# Aux_Board_V5.net
KiCad netlist of a schematic drawn in EAGLE
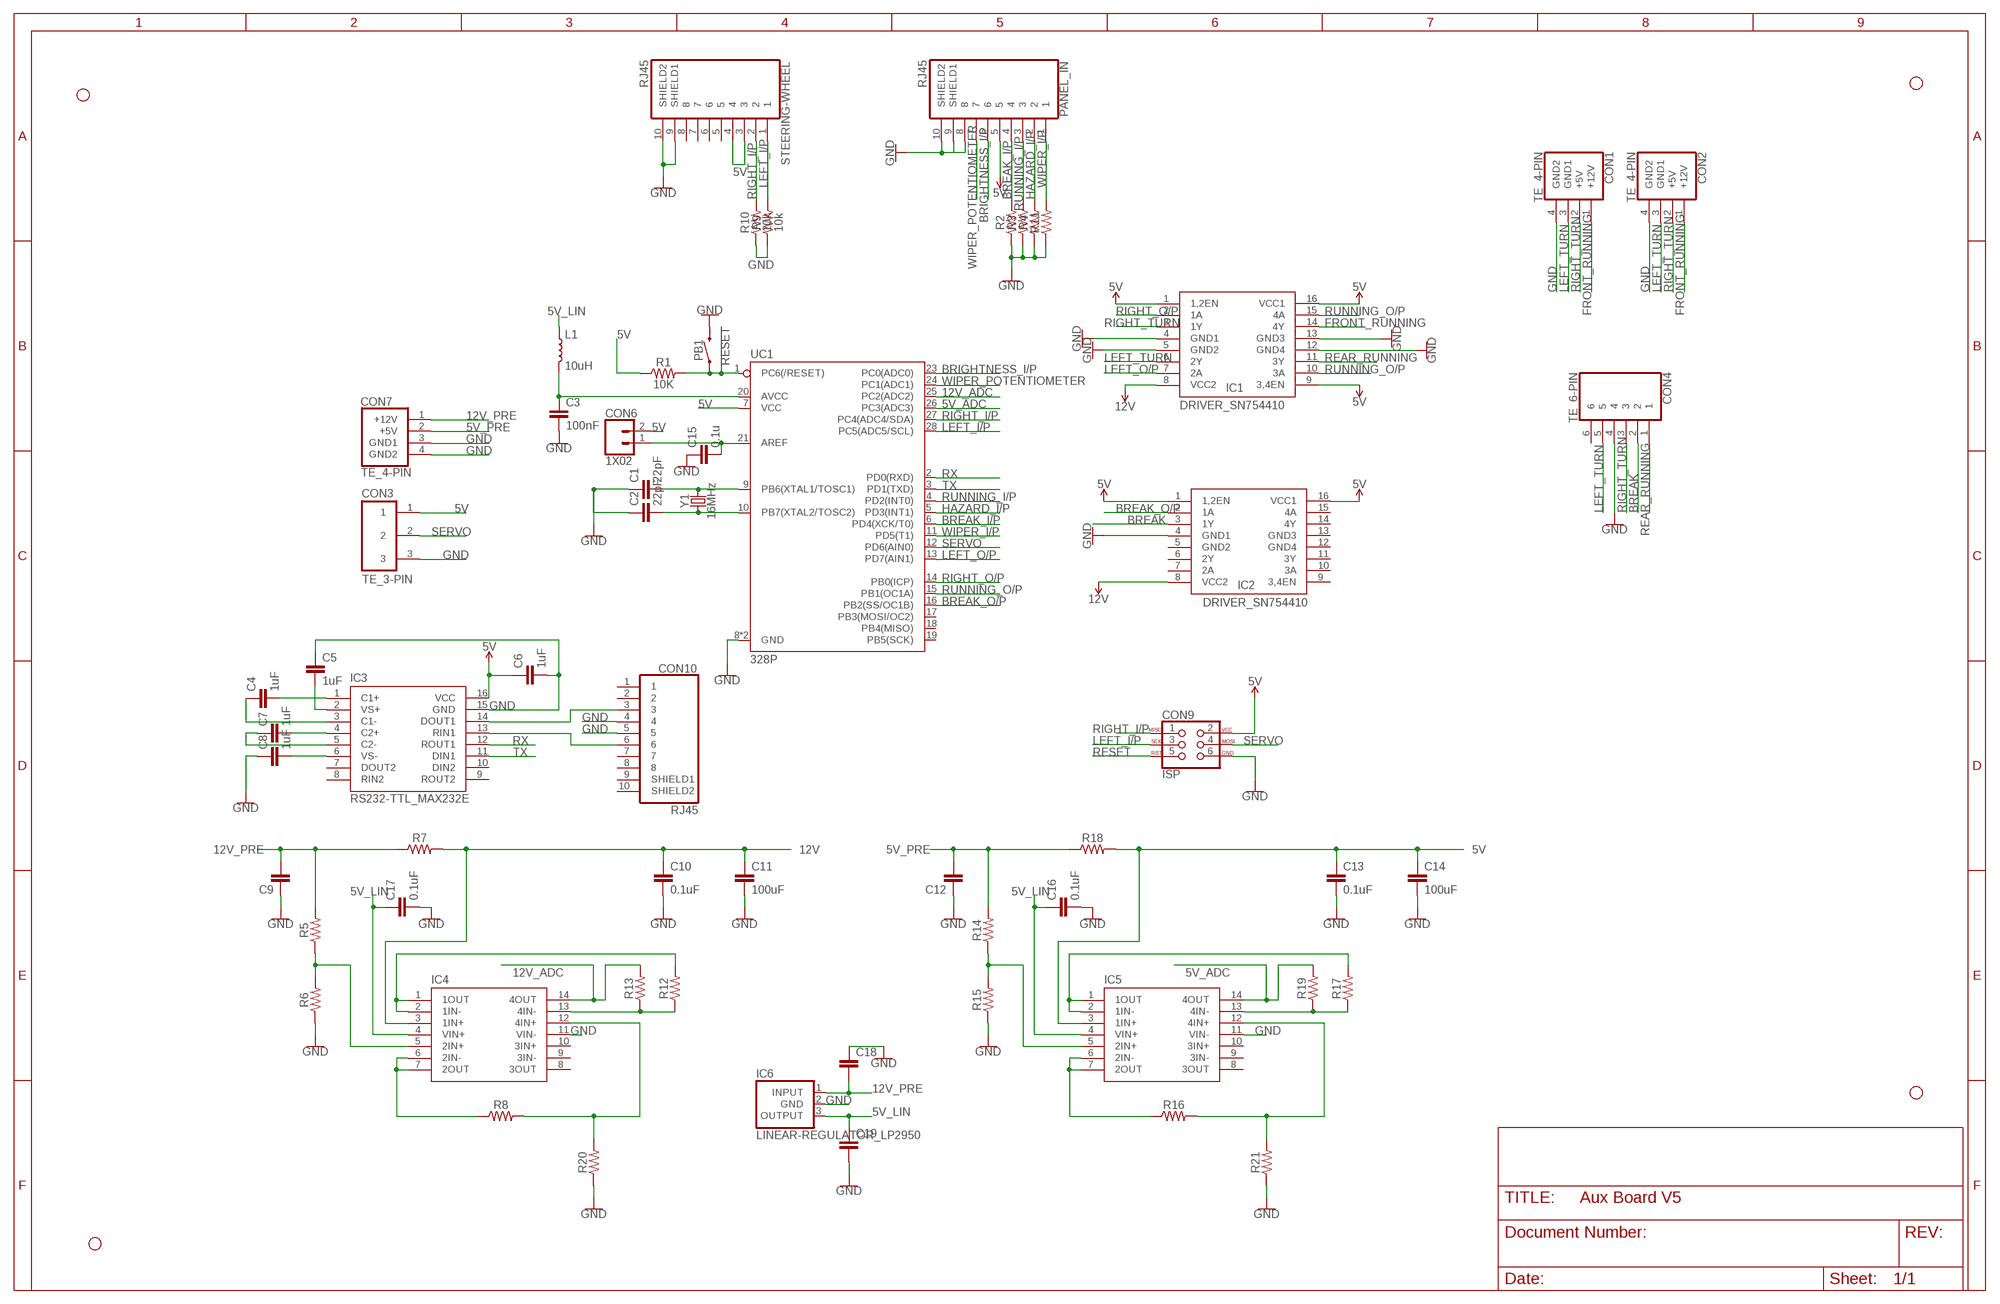
[diagram p0: schematic, sheet 1]

(export (version "E")
  (design (tool "Eeschema 10.0.6"))
  (components
    (comp (ref "C1")
      (value "22pF")
      (footprint "eagle-import:0805")
      (libsource (lib "eagle-import") (part "CAPACITOR_0805"))
    )
    (comp (ref "C2")
      (value "22pF")
      (footprint "eagle-import:0805")
      (libsource (lib "eagle-import") (part "CAPACITOR_0805"))
    )
    (comp (ref "C3")
      (value "100nF")
      (footprint "eagle-import:0805")
      (libsource (lib "eagle-import") (part "CAPACITOR_0805"))
    )
    (comp (ref "C4")
      (value "1uF")
      (footprint "eagle-import:0805")
      (libsource (lib "eagle-import") (part "CAPACITOR_0805"))
    )
    (comp (ref "C5")
      (value "1uF")
      (footprint "eagle-import:0805")
      (libsource (lib "eagle-import") (part "CAPACITOR_0805"))
    )
    (comp (ref "C6")
      (value "1uF")
      (footprint "eagle-import:0805")
      (libsource (lib "eagle-import") (part "CAPACITOR_0805"))
    )
    (comp (ref "C7")
      (value "1uF")
      (footprint "eagle-import:0805")
      (libsource (lib "eagle-import") (part "CAPACITOR_0805"))
    )
    (comp (ref "C8")
      (value "1uF")
      (footprint "eagle-import:0805")
      (libsource (lib "eagle-import") (part "CAPACITOR_0805"))
    )
    (comp (ref "C9")
      (value "CAPACITOR_0805")
      (footprint "eagle-import:0805")
      (libsource (lib "eagle-import") (part "CAPACITOR_0805"))
    )
    (comp (ref "C10")
      (value "0.1uF")
      (footprint "eagle-import:0805")
      (libsource (lib "eagle-import") (part "CAPACITOR_0805"))
    )
    (comp (ref "C11")
      (value "100uF")
      (footprint "eagle-import:0805")
      (libsource (lib "eagle-import") (part "CAPACITOR_0805"))
    )
    (comp (ref "C12")
      (value "CAPACITOR_0805")
      (footprint "eagle-import:0805")
      (libsource (lib "eagle-import") (part "CAPACITOR_0805"))
    )
    (comp (ref "C13")
      (value "0.1uF")
      (footprint "eagle-import:0805")
      (libsource (lib "eagle-import") (part "CAPACITOR_0805"))
    )
    (comp (ref "C14")
      (value "100uF")
      (footprint "eagle-import:0805")
      (libsource (lib "eagle-import") (part "CAPACITOR_0805"))
    )
    (comp (ref "C15")
      (value "0.1u")
      (footprint "eagle-import:0805")
      (libsource (lib "eagle-import") (part "CAPACITOR_0805"))
    )
    (comp (ref "C16")
      (value "0.1uF")
      (footprint "eagle-import:0805")
      (libsource (lib "eagle-import") (part "CAPACITOR_0805"))
    )
    (comp (ref "C17")
      (value "0.1uF")
      (footprint "eagle-import:0805")
      (libsource (lib "eagle-import") (part "CAPACITOR_0805"))
    )
    (comp (ref "C18")
      (value "CAPACITOR_0805")
      (footprint "eagle-import:0805")
      (libsource (lib "eagle-import") (part "CAPACITOR_0805"))
    )
    (comp (ref "C19")
      (value "CAPACITOR_0805")
      (footprint "eagle-import:0805")
      (libsource (lib "eagle-import") (part "CAPACITOR_0805"))
    )
    (comp (ref "CON1")
      (value "TE_4-PIN")
      (footprint "eagle-import:TE_4-PIN")
      (libsource (lib "eagle-import") (part "TE_4-PIN"))
    )
    (comp (ref "CON2")
      (value "TE_4-PIN")
      (footprint "eagle-import:TE_4-PIN")
      (libsource (lib "eagle-import") (part "TE_4-PIN"))
    )
    (comp (ref "CON3")
      (value "TE_3-PIN")
      (footprint "eagle-import:TE_3-PIN")
      (libsource (lib "eagle-import") (part "TE_3-PIN"))
    )
    (comp (ref "CON4")
      (value "TE_6-PIN")
      (footprint "eagle-import:TE_6-PIN")
      (libsource (lib "eagle-import") (part "TE_6-PIN"))
    )
    (comp (ref "CON6")
      (value "1X02")
      (footprint "eagle-import:1X02")
      (libsource (lib "eagle-import") (part "1X02"))
    )
    (comp (ref "CON7")
      (value "TE_4-PIN")
      (footprint "eagle-import:TE_4-PIN")
      (libsource (lib "eagle-import") (part "TE_4-PIN"))
    )
    (comp (ref "CON9")
      (value "ISP")
      (footprint "eagle-import:ISP_CONNECTOR")
      (libsource (lib "eagle-import") (part "ISP"))
    )
    (comp (ref "CON10")
      (value "RJ45")
      (footprint "eagle-import:RJ45")
      (libsource (lib "eagle-import") (part "RJ45"))
    )
    (comp (ref "H1")
      (value "STAND-OFF")
      (footprint "eagle-import:STAND-OFF")
      (libsource (lib "eagle-import") (part "STAND-OFF"))
    )
    (comp (ref "H2")
      (value "STAND-OFF")
      (footprint "eagle-import:STAND-OFF")
      (libsource (lib "eagle-import") (part "STAND-OFF"))
    )
    (comp (ref "H3")
      (value "STAND-OFF")
      (footprint "eagle-import:STAND-OFF")
      (libsource (lib "eagle-import") (part "STAND-OFF"))
    )
    (comp (ref "H4")
      (value "STAND-OFF")
      (footprint "eagle-import:STAND-OFF")
      (libsource (lib "eagle-import") (part "STAND-OFF"))
    )
    (comp (ref "IC1")
      (value "DRIVER_SN754410")
      (footprint "eagle-import:DIP16")
      (libsource (lib "eagle-import") (part "DRIVER_SN754410"))
    )
    (comp (ref "IC2")
      (value "DRIVER_SN754410")
      (footprint "eagle-import:DIP16")
      (libsource (lib "eagle-import") (part "DRIVER_SN754410"))
    )
    (comp (ref "IC3")
      (value "RS232-TTL_MAX232E")
      (footprint "eagle-import:DIP16")
      (libsource (lib "eagle-import") (part "RS232-TTL_MAX232E"))
    )
    (comp (ref "IC4")
      (value "OP-AMP_QUAD")
      (footprint "eagle-import:DIP14")
      (libsource (lib "eagle-import") (part "OP-AMP_QUAD"))
    )
    (comp (ref "IC5")
      (value "OP-AMP_QUAD")
      (footprint "eagle-import:DIP14")
      (libsource (lib "eagle-import") (part "OP-AMP_QUAD"))
    )
    (comp (ref "IC6")
      (value "LINEAR-REGULATOR_LP2950")
      (footprint "eagle-import:TO92")
      (libsource (lib "eagle-import") (part "LINEAR-REGULATOR_LP2950"))
    )
    (comp (ref "L1")
      (value "10uH")
      (footprint "eagle-import:0805")
      (libsource (lib "eagle-import") (part "INDUCTOR_0805"))
    )
    (comp (ref "PANEL_IN")
      (value "RJ45")
      (footprint "eagle-import:RJ45")
      (libsource (lib "eagle-import") (part "RJ45"))
    )
    (comp (ref "PB1")
      (value "PUSHBUTTON")
      (footprint "eagle-import:PUSHBUTTON")
      (libsource (lib "eagle-import") (part "PUSHBUTTON"))
    )
    (comp (ref "R1")
      (value "10K")
      (footprint "eagle-import:0805")
      (libsource (lib "eagle-import") (part "RESISTOR_0805"))
    )
    (comp (ref "R2")
      (value "RESISTOR_0805")
      (footprint "eagle-import:0805")
      (libsource (lib "eagle-import") (part "RESISTOR_0805"))
    )
    (comp (ref "R3")
      (value "RESISTOR_0805")
      (footprint "eagle-import:0805")
      (libsource (lib "eagle-import") (part "RESISTOR_0805"))
    )
    (comp (ref "R4")
      (value "RESISTOR_0805")
      (footprint "eagle-import:0805")
      (libsource (lib "eagle-import") (part "RESISTOR_0805"))
    )
    (comp (ref "R5")
      (value "RESISTOR_0805")
      (footprint "eagle-import:0805")
      (libsource (lib "eagle-import") (part "RESISTOR_0805"))
    )
    (comp (ref "R6")
      (value "RESISTOR_0805")
      (footprint "eagle-import:0805")
      (libsource (lib "eagle-import") (part "RESISTOR_0805"))
    )
    (comp (ref "R7")
      (value "RESISTOR_1210")
      (footprint "eagle-import:1210")
      (libsource (lib "eagle-import") (part "RESISTOR_1210"))
    )
    (comp (ref "R8")
      (value "RESISTOR_0805")
      (footprint "eagle-import:0805")
      (libsource (lib "eagle-import") (part "RESISTOR_0805"))
    )
    (comp (ref "R9")
      (value "10k")
      (footprint "eagle-import:0805")
      (libsource (lib "eagle-import") (part "RESISTOR_0805"))
    )
    (comp (ref "R10")
      (value "10k")
      (footprint "eagle-import:0805")
      (libsource (lib "eagle-import") (part "RESISTOR_0805"))
    )
    (comp (ref "R11")
      (value "RESISTOR_0805")
      (footprint "eagle-import:0805")
      (libsource (lib "eagle-import") (part "RESISTOR_0805"))
    )
    (comp (ref "R12")
      (value "RESISTOR_0805")
      (footprint "eagle-import:0805")
      (libsource (lib "eagle-import") (part "RESISTOR_0805"))
    )
    (comp (ref "R13")
      (value "RESISTOR_0805")
      (footprint "eagle-import:0805")
      (libsource (lib "eagle-import") (part "RESISTOR_0805"))
    )
    (comp (ref "R14")
      (value "RESISTOR_0805")
      (footprint "eagle-import:0805")
      (libsource (lib "eagle-import") (part "RESISTOR_0805"))
    )
    (comp (ref "R15")
      (value "RESISTOR_0805")
      (footprint "eagle-import:0805")
      (libsource (lib "eagle-import") (part "RESISTOR_0805"))
    )
    (comp (ref "R16")
      (value "RESISTOR_0805")
      (footprint "eagle-import:0805")
      (libsource (lib "eagle-import") (part "RESISTOR_0805"))
    )
    (comp (ref "R17")
      (value "RESISTOR_0805")
      (footprint "eagle-import:0805")
      (libsource (lib "eagle-import") (part "RESISTOR_0805"))
    )
    (comp (ref "R18")
      (value "RESISTOR_1210")
      (footprint "eagle-import:1210")
      (libsource (lib "eagle-import") (part "RESISTOR_1210"))
    )
    (comp (ref "R19")
      (value "RESISTOR_0805")
      (footprint "eagle-import:0805")
      (libsource (lib "eagle-import") (part "RESISTOR_0805"))
    )
    (comp (ref "R20")
      (value "RESISTOR_0805")
      (footprint "eagle-import:0805")
      (libsource (lib "eagle-import") (part "RESISTOR_0805"))
    )
    (comp (ref "R21")
      (value "RESISTOR_0805")
      (footprint "eagle-import:0805")
      (libsource (lib "eagle-import") (part "RESISTOR_0805"))
    )
    (comp (ref "STEERING-WHEEL")
      (value "RJ45")
      (footprint "eagle-import:RJ45")
      (libsource (lib "eagle-import") (part "RJ45"))
    )
    (comp (ref "UC1")
      (value "328P")
      (footprint "eagle-import:DIP28")
      (libsource (lib "eagle-import") (part "ATMEGA328P_DIP28"))
    )
    (comp (ref "Y1")
      (value "16MHz")
      (footprint "eagle-import:HC49US")
      (libsource (lib "eagle-import") (part "CRYSTAL-16MHZPTH-HC49US"))
    )
  )
  (nets
    (net (code "1") (name "/5V_ADC") (class "Default")
      (node (ref "IC5") (pin "14") (pinfunction "4OUT_14") (pintype "bidirectional"))
      (node (ref "R19") (pin "2") (pinfunction "2_2") (pintype "passive"))
      (node (ref "UC1") (pin "26") (pinfunction "PC3(ADC3)_26") (pintype "bidirectional"))
    )
    (net (code "2") (name "/5V_LIN") (class "Default")
      (node (ref "C16") (pin "1") (pinfunction "1_1") (pintype "passive"))
      (node (ref "C17") (pin "1") (pinfunction "1_1") (pintype "passive"))
      (node (ref "C19") (pin "1") (pinfunction "1_1") (pintype "passive"))
      (node (ref "IC4") (pin "4") (pinfunction "VIN+_4") (pintype "bidirectional"))
      (node (ref "IC5") (pin "4") (pinfunction "VIN+_4") (pintype "bidirectional"))
      (node (ref "IC6") (pin "3") (pinfunction "OUTPUT_3") (pintype "bidirectional"))
      (node (ref "L1") (pin "1") (pinfunction "1_1") (pintype "passive"))
    )
    (net (code "3") (name "/5V_PRE") (class "Default")
      (node (ref "C12") (pin "2") (pinfunction "2_2") (pintype "passive"))
      (node (ref "CON7") (pin "2") (pinfunction "+5V_2") (pintype "passive"))
      (node (ref "R14") (pin "2") (pinfunction "2_2") (pintype "passive"))
      (node (ref "R18") (pin "1") (pinfunction "1_1") (pintype "passive"))
    )
    (net (code "4") (name "/12V_ADC") (class "Default")
      (node (ref "IC4") (pin "14") (pinfunction "4OUT_14") (pintype "bidirectional"))
      (node (ref "R13") (pin "2") (pinfunction "2_2") (pintype "passive"))
      (node (ref "UC1") (pin "25") (pinfunction "PC2(ADC2)_25") (pintype "bidirectional"))
    )
    (net (code "5") (name "/12V_PRE") (class "Default")
      (node (ref "C18") (pin "2") (pinfunction "2_2") (pintype "passive"))
      (node (ref "C9") (pin "2") (pinfunction "2_2") (pintype "passive"))
      (node (ref "CON7") (pin "1") (pinfunction "+12V_1") (pintype "passive"))
      (node (ref "IC6") (pin "1") (pinfunction "INPUT_1") (pintype "bidirectional"))
      (node (ref "R5") (pin "2") (pinfunction "2_2") (pintype "passive"))
      (node (ref "R7") (pin "1") (pinfunction "1_1") (pintype "passive"))
    )
    (net (code "6") (name "/BREAK") (class "Default")
      (node (ref "CON4") (pin "2") (pinfunction "2_2") (pintype "passive"))
      (node (ref "IC2") (pin "3") (pinfunction "1Y_3") (pintype "bidirectional"))
    )
    (net (code "7") (name "/BREAK_I{slash}P") (class "Default")
      (node (ref "PANEL_IN") (pin "4") (pinfunction "4_4") (pintype "passive"))
      (node (ref "R2") (pin "2") (pinfunction "2_2") (pintype "passive"))
      (node (ref "UC1") (pin "6") (pinfunction "PD4(XCK/T0)_6") (pintype "bidirectional"))
    )
    (net (code "8") (name "/BREAK_O{slash}P") (class "Default")
      (node (ref "IC2") (pin "2") (pinfunction "1A_2") (pintype "bidirectional"))
      (node (ref "UC1") (pin "16") (pinfunction "PB2(SS/OC1B)_16") (pintype "bidirectional"))
    )
    (net (code "9") (name "/BRIGHTNESS_I{slash}P") (class "Default")
      (node (ref "PANEL_IN") (pin "6") (pinfunction "6_6") (pintype "passive"))
      (node (ref "UC1") (pin "23") (pinfunction "PC0(ADC0)_23") (pintype "bidirectional"))
    )
    (net (code "10") (name "/FRONT_RUNNING") (class "Default")
      (node (ref "CON1") (pin "1") (pinfunction "+12V_1") (pintype "passive"))
      (node (ref "CON2") (pin "1") (pinfunction "+12V_1") (pintype "passive"))
      (node (ref "IC1") (pin "14") (pinfunction "4Y_14") (pintype "bidirectional"))
    )
    (net (code "11") (name "/HAZARD_I{slash}P") (class "Default")
      (node (ref "PANEL_IN") (pin "2") (pinfunction "2_2") (pintype "passive"))
      (node (ref "R4") (pin "2") (pinfunction "2_2") (pintype "passive"))
      (node (ref "UC1") (pin "5") (pinfunction "PD3(INT1)_5") (pintype "bidirectional"))
    )
    (net (code "12") (name "/LEFT_I{slash}P") (class "Default")
      (node (ref "CON9") (pin "3") (pinfunction "3_3") (pintype "passive"))
      (node (ref "R9") (pin "2") (pinfunction "2_2") (pintype "passive"))
      (node (ref "STEERING-WHEEL") (pin "1") (pinfunction "1_1") (pintype "passive"))
      (node (ref "UC1") (pin "28") (pinfunction "PC5(ADC5/SCL)_28") (pintype "bidirectional"))
    )
    (net (code "13") (name "/LEFT_O{slash}P") (class "Default")
      (node (ref "IC1") (pin "7") (pinfunction "2A_7") (pintype "bidirectional"))
      (node (ref "UC1") (pin "13") (pinfunction "PD7(AIN1)_13") (pintype "bidirectional"))
    )
    (net (code "14") (name "/LEFT_TURN") (class "Default")
      (node (ref "CON1") (pin "3") (pinfunction "GND1_3") (pintype "passive"))
      (node (ref "CON2") (pin "3") (pinfunction "GND1_3") (pintype "passive"))
      (node (ref "CON4") (pin "5") (pinfunction "5_5") (pintype "passive"))
      (node (ref "IC1") (pin "6") (pinfunction "2Y_6") (pintype "bidirectional"))
    )
    (net (code "15") (name "/REAR_RUNNING") (class "Default")
      (node (ref "CON4") (pin "1") (pinfunction "1_1") (pintype "passive"))
      (node (ref "IC1") (pin "11") (pinfunction "3Y_11") (pintype "bidirectional"))
    )
    (net (code "16") (name "/RESET") (class "Default")
      (node (ref "CON9") (pin "5") (pinfunction "5_5") (pintype "passive"))
      (node (ref "PB1") (pin "1") (pinfunction "1_1") (pintype "passive"))
      (node (ref "PB1") (pin "2") (pinfunction "1_2") (pintype "passive"))
      (node (ref "R1") (pin "2") (pinfunction "2_2") (pintype "passive"))
      (node (ref "UC1") (pin "1") (pinfunction "PC6(/RESET)_1") (pintype "bidirectional"))
    )
    (net (code "17") (name "/RIGHT_I{slash}P") (class "Default")
      (node (ref "CON9") (pin "1") (pinfunction "1_1") (pintype "passive"))
      (node (ref "R10") (pin "2") (pinfunction "2_2") (pintype "passive"))
      (node (ref "STEERING-WHEEL") (pin "2") (pinfunction "2_2") (pintype "passive"))
      (node (ref "UC1") (pin "27") (pinfunction "PC4(ADC4/SDA)_27") (pintype "bidirectional"))
    )
    (net (code "18") (name "/RIGHT_O{slash}P") (class "Default")
      (node (ref "IC1") (pin "2") (pinfunction "1A_2") (pintype "bidirectional"))
      (node (ref "UC1") (pin "14") (pinfunction "PB0(ICP)_14") (pintype "bidirectional"))
    )
    (net (code "19") (name "/RIGHT_TURN") (class "Default")
      (node (ref "CON1") (pin "2") (pinfunction "+5V_2") (pintype "passive"))
      (node (ref "CON2") (pin "2") (pinfunction "+5V_2") (pintype "passive"))
      (node (ref "CON4") (pin "3") (pinfunction "3_3") (pintype "passive"))
      (node (ref "IC1") (pin "3") (pinfunction "1Y_3") (pintype "bidirectional"))
    )
    (net (code "20") (name "/RUNNING_I{slash}P") (class "Default")
      (node (ref "PANEL_IN") (pin "3") (pinfunction "3_3") (pintype "passive"))
      (node (ref "R3") (pin "2") (pinfunction "2_2") (pintype "passive"))
      (node (ref "UC1") (pin "4") (pinfunction "PD2(INT0)_4") (pintype "bidirectional"))
    )
    (net (code "21") (name "/RUNNING_O{slash}P") (class "Default")
      (node (ref "IC1") (pin "10") (pinfunction "3A_10") (pintype "bidirectional"))
      (node (ref "IC1") (pin "15") (pinfunction "4A_15") (pintype "bidirectional"))
      (node (ref "UC1") (pin "15") (pinfunction "PB1(OC1A)_15") (pintype "bidirectional"))
    )
    (net (code "22") (name "/RX") (class "Default")
      (node (ref "IC3") (pin "12") (pinfunction "ROUT1_12") (pintype "bidirectional"))
      (node (ref "UC1") (pin "2") (pinfunction "PD0(RXD)_2") (pintype "bidirectional"))
    )
    (net (code "23") (name "/SERVO") (class "Default")
      (node (ref "CON3") (pin "2") (pinfunction "2_2") (pintype "passive"))
      (node (ref "CON9") (pin "4") (pinfunction "4_4") (pintype "passive"))
      (node (ref "UC1") (pin "12") (pinfunction "PD6(AIN0)_12") (pintype "bidirectional"))
    )
    (net (code "24") (name "/TX") (class "Default")
      (node (ref "IC3") (pin "11") (pinfunction "DIN1_11") (pintype "bidirectional"))
      (node (ref "UC1") (pin "3") (pinfunction "PD1(TXD)_3") (pintype "bidirectional"))
    )
    (net (code "25") (name "/WIPER_I{slash}P") (class "Default")
      (node (ref "PANEL_IN") (pin "1") (pinfunction "1_1") (pintype "passive"))
      (node (ref "R11") (pin "2") (pinfunction "2_2") (pintype "passive"))
      (node (ref "UC1") (pin "11") (pinfunction "PD5(T1)_11") (pintype "bidirectional"))
    )
    (net (code "26") (name "/WIPER_POTENTIOMETER") (class "Default")
      (node (ref "PANEL_IN") (pin "7") (pinfunction "7_7") (pintype "passive"))
      (node (ref "UC1") (pin "24") (pinfunction "PC1(ADC1)_24") (pintype "bidirectional"))
    )
    (net (code "27") (name "5V") (class "Default")
      (node (ref "C13") (pin "1") (pinfunction "1_1") (pintype "passive"))
      (node (ref "C14") (pin "1") (pinfunction "1_1") (pintype "passive"))
      (node (ref "C15") (pin "2") (pinfunction "2_2") (pintype "passive"))
      (node (ref "C6") (pin "1") (pinfunction "1_1") (pintype "passive"))
      (node (ref "CON3") (pin "1") (pinfunction "1_1") (pintype "passive"))
      (node (ref "CON6") (pin "1") (pinfunction "1_1") (pintype "passive"))
      (node (ref "CON6") (pin "2") (pinfunction "2_2") (pintype "passive"))
      (node (ref "CON9") (pin "2") (pinfunction "2_2") (pintype "passive"))
      (node (ref "IC1") (pin "1") (pinfunction "1,2EN_1") (pintype "bidirectional"))
      (node (ref "IC1") (pin "16") (pinfunction "VCC1_16") (pintype "bidirectional"))
      (node (ref "IC1") (pin "9") (pinfunction "3,4EN_9") (pintype "bidirectional"))
      (node (ref "IC2") (pin "1") (pinfunction "1,2EN_1") (pintype "bidirectional"))
      (node (ref "IC2") (pin "16") (pinfunction "VCC1_16") (pintype "bidirectional"))
      (node (ref "IC3") (pin "16") (pinfunction "VCC_16") (pintype "bidirectional"))
      (node (ref "IC5") (pin "3") (pinfunction "1IN+_3") (pintype "bidirectional"))
      (node (ref "PANEL_IN") (pin "5") (pinfunction "5_5") (pintype "passive"))
      (node (ref "R1") (pin "1") (pinfunction "1_1") (pintype "passive"))
      (node (ref "R18") (pin "2") (pinfunction "2_2") (pintype "passive"))
      (node (ref "STEERING-WHEEL") (pin "3") (pinfunction "3_3") (pintype "passive"))
      (node (ref "STEERING-WHEEL") (pin "4") (pinfunction "4_4") (pintype "passive"))
      (node (ref "UC1") (pin "21") (pinfunction "AREF_21") (pintype "bidirectional"))
      (node (ref "UC1") (pin "7") (pinfunction "VCC_7") (pintype "bidirectional"))
    )
    (net (code "28") (name "12V") (class "Default")
      (node (ref "C10") (pin "1") (pinfunction "1_1") (pintype "passive"))
      (node (ref "C11") (pin "1") (pinfunction "1_1") (pintype "passive"))
      (node (ref "IC1") (pin "8") (pinfunction "VCC2_8") (pintype "bidirectional"))
      (node (ref "IC2") (pin "8") (pinfunction "VCC2_8") (pintype "bidirectional"))
      (node (ref "IC4") (pin "3") (pinfunction "1IN+_3") (pintype "bidirectional"))
      (node (ref "R7") (pin "2") (pinfunction "2_2") (pintype "passive"))
    )
    (net (code "29") (name "GND") (class "Default")
      (node (ref "C1") (pin "1") (pinfunction "1_1") (pintype "passive"))
      (node (ref "C10") (pin "2") (pinfunction "2_2") (pintype "passive"))
      (node (ref "C11") (pin "2") (pinfunction "2_2") (pintype "passive"))
      (node (ref "C12") (pin "1") (pinfunction "1_1") (pintype "passive"))
      (node (ref "C13") (pin "2") (pinfunction "2_2") (pintype "passive"))
      (node (ref "C14") (pin "2") (pinfunction "2_2") (pintype "passive"))
      (node (ref "C15") (pin "1") (pinfunction "1_1") (pintype "passive"))
      (node (ref "C16") (pin "2") (pinfunction "2_2") (pintype "passive"))
      (node (ref "C17") (pin "2") (pinfunction "2_2") (pintype "passive"))
      (node (ref "C18") (pin "1") (pinfunction "1_1") (pintype "passive"))
      (node (ref "C19") (pin "2") (pinfunction "2_2") (pintype "passive"))
      (node (ref "C2") (pin "1") (pinfunction "1_1") (pintype "passive"))
      (node (ref "C3") (pin "2") (pinfunction "2_2") (pintype "passive"))
      (node (ref "C5") (pin "1") (pinfunction "1_1") (pintype "passive"))
      (node (ref "C6") (pin "2") (pinfunction "2_2") (pintype "passive"))
      (node (ref "C8") (pin "1") (pinfunction "1_1") (pintype "passive"))
      (node (ref "C9") (pin "1") (pinfunction "1_1") (pintype "passive"))
      (node (ref "CON1") (pin "4") (pinfunction "GND2_4") (pintype "passive"))
      (node (ref "CON10") (pin "4") (pinfunction "4_4") (pintype "passive"))
      (node (ref "CON10") (pin "5") (pinfunction "5_5") (pintype "passive"))
      (node (ref "CON2") (pin "4") (pinfunction "GND2_4") (pintype "passive"))
      (node (ref "CON3") (pin "3") (pinfunction "3_3") (pintype "passive"))
      (node (ref "CON4") (pin "4") (pinfunction "4_4") (pintype "passive"))
      (node (ref "CON7") (pin "3") (pinfunction "GND1_3") (pintype "passive"))
      (node (ref "CON7") (pin "4") (pinfunction "GND2_4") (pintype "passive"))
      (node (ref "CON9") (pin "6") (pinfunction "6_6") (pintype "passive"))
      (node (ref "IC1") (pin "12") (pinfunction "GND4_12") (pintype "bidirectional"))
      (node (ref "IC1") (pin "13") (pinfunction "GND3_13") (pintype "bidirectional"))
      (node (ref "IC1") (pin "4") (pinfunction "GND1_4") (pintype "bidirectional"))
      (node (ref "IC1") (pin "5") (pinfunction "GND2_5") (pintype "bidirectional"))
      (node (ref "IC2") (pin "4") (pinfunction "GND1_4") (pintype "bidirectional"))
      (node (ref "IC3") (pin "15") (pinfunction "GND_15") (pintype "bidirectional"))
      (node (ref "IC4") (pin "11") (pinfunction "VIN-_11") (pintype "bidirectional"))
      (node (ref "IC5") (pin "11") (pinfunction "VIN-_11") (pintype "bidirectional"))
      (node (ref "IC6") (pin "2") (pinfunction "GND_2") (pintype "bidirectional"))
      (node (ref "PANEL_IN") (pin "10") (pinfunction "SHIELD2_10") (pintype "passive"))
      (node (ref "PANEL_IN") (pin "8") (pinfunction "8_8") (pintype "passive"))
      (node (ref "PANEL_IN") (pin "9") (pinfunction "SHIELD1_9") (pintype "passive"))
      (node (ref "PB1") (pin "3") (pinfunction "2_3") (pintype "passive"))
      (node (ref "PB1") (pin "4") (pinfunction "2_4") (pintype "passive"))
      (node (ref "R10") (pin "1") (pinfunction "1_1") (pintype "passive"))
      (node (ref "R11") (pin "1") (pinfunction "1_1") (pintype "passive"))
      (node (ref "R15") (pin "1") (pinfunction "1_1") (pintype "passive"))
      (node (ref "R2") (pin "1") (pinfunction "1_1") (pintype "passive"))
      (node (ref "R20") (pin "1") (pinfunction "1_1") (pintype "passive"))
      (node (ref "R21") (pin "1") (pinfunction "1_1") (pintype "passive"))
      (node (ref "R3") (pin "1") (pinfunction "1_1") (pintype "passive"))
      (node (ref "R4") (pin "1") (pinfunction "1_1") (pintype "passive"))
      (node (ref "R6") (pin "1") (pinfunction "1_1") (pintype "passive"))
      (node (ref "R9") (pin "1") (pinfunction "1_1") (pintype "passive"))
      (node (ref "STEERING-WHEEL") (pin "10") (pinfunction "SHIELD2_10") (pintype "passive"))
      (node (ref "STEERING-WHEEL") (pin "9") (pinfunction "SHIELD1_9") (pintype "passive"))
      (node (ref "UC1") (pin "22") (pinfunction "GND_22") (pintype "bidirectional"))
      (node (ref "UC1") (pin "8") (pinfunction "GND_8") (pintype "bidirectional"))
    )
    (net (code "30") (name "Net-(IC3-C1+)") (class "Default")
      (node (ref "C4") (pin "2") (pinfunction "2_2") (pintype "passive"))
      (node (ref "IC3") (pin "1") (pinfunction "C1+_1") (pintype "bidirectional"))
    )
    (net (code "31") (name "Net-(IC3-C1-)") (class "Default")
      (node (ref "C4") (pin "1") (pinfunction "1_1") (pintype "passive"))
      (node (ref "IC3") (pin "3") (pinfunction "C1-_3") (pintype "bidirectional"))
    )
    (net (code "32") (name "Net-(IC3-C2+)") (class "Default")
      (node (ref "C7") (pin "2") (pinfunction "2_2") (pintype "passive"))
      (node (ref "IC3") (pin "4") (pinfunction "C2+_4") (pintype "bidirectional"))
    )
    (net (code "33") (name "Net-(IC3-C2-)") (class "Default")
      (node (ref "C7") (pin "1") (pinfunction "1_1") (pintype "passive"))
      (node (ref "IC3") (pin "5") (pinfunction "C2-_5") (pintype "bidirectional"))
    )
    (net (code "34") (name "Net-(IC3-DOUT1)") (class "Default")
      (node (ref "CON10") (pin "3") (pinfunction "3_3") (pintype "passive"))
      (node (ref "IC3") (pin "14") (pinfunction "DOUT1_14") (pintype "bidirectional"))
    )
    (net (code "35") (name "Net-(IC3-RIN1)") (class "Default")
      (node (ref "CON10") (pin "6") (pinfunction "6_6") (pintype "passive"))
      (node (ref "IC3") (pin "13") (pinfunction "RIN1_13") (pintype "bidirectional"))
    )
    (net (code "36") (name "Net-(IC3-VS+)") (class "Default")
      (node (ref "C5") (pin "2") (pinfunction "2_2") (pintype "passive"))
      (node (ref "IC3") (pin "2") (pinfunction "VS+_2") (pintype "bidirectional"))
    )
    (net (code "37") (name "Net-(IC3-VS-)") (class "Default")
      (node (ref "C8") (pin "2") (pinfunction "2_2") (pintype "passive"))
      (node (ref "IC3") (pin "6") (pinfunction "VS-_6") (pintype "bidirectional"))
    )
    (net (code "38") (name "Net-(IC4-1IN-)") (class "Default")
      (node (ref "IC4") (pin "1") (pinfunction "1OUT_1") (pintype "bidirectional"))
      (node (ref "IC4") (pin "2") (pinfunction "1IN-_2") (pintype "bidirectional"))
      (node (ref "R12") (pin "2") (pinfunction "2_2") (pintype "passive"))
    )
    (net (code "39") (name "Net-(IC4-2IN+)") (class "Default")
      (node (ref "IC4") (pin "5") (pinfunction "2IN+_5") (pintype "bidirectional"))
      (node (ref "R5") (pin "1") (pinfunction "1_1") (pintype "passive"))
      (node (ref "R6") (pin "2") (pinfunction "2_2") (pintype "passive"))
    )
    (net (code "40") (name "Net-(IC4-2IN-)") (class "Default")
      (node (ref "IC4") (pin "6") (pinfunction "2IN-_6") (pintype "bidirectional"))
      (node (ref "IC4") (pin "7") (pinfunction "2OUT_7") (pintype "bidirectional"))
      (node (ref "R8") (pin "1") (pinfunction "1_1") (pintype "passive"))
    )
    (net (code "41") (name "Net-(IC4-4IN+)") (class "Default")
      (node (ref "IC4") (pin "12") (pinfunction "4IN+_12") (pintype "bidirectional"))
      (node (ref "R20") (pin "2") (pinfunction "2_2") (pintype "passive"))
      (node (ref "R8") (pin "2") (pinfunction "2_2") (pintype "passive"))
    )
    (net (code "42") (name "Net-(IC4-4IN-)") (class "Default")
      (node (ref "IC4") (pin "13") (pinfunction "4IN-_13") (pintype "bidirectional"))
      (node (ref "R12") (pin "1") (pinfunction "1_1") (pintype "passive"))
      (node (ref "R13") (pin "1") (pinfunction "1_1") (pintype "passive"))
    )
    (net (code "43") (name "Net-(IC5-1IN-)") (class "Default")
      (node (ref "IC5") (pin "1") (pinfunction "1OUT_1") (pintype "bidirectional"))
      (node (ref "IC5") (pin "2") (pinfunction "1IN-_2") (pintype "bidirectional"))
      (node (ref "R17") (pin "2") (pinfunction "2_2") (pintype "passive"))
    )
    (net (code "44") (name "Net-(IC5-2IN+)") (class "Default")
      (node (ref "IC5") (pin "5") (pinfunction "2IN+_5") (pintype "bidirectional"))
      (node (ref "R14") (pin "1") (pinfunction "1_1") (pintype "passive"))
      (node (ref "R15") (pin "2") (pinfunction "2_2") (pintype "passive"))
    )
    (net (code "45") (name "Net-(IC5-2IN-)") (class "Default")
      (node (ref "IC5") (pin "6") (pinfunction "2IN-_6") (pintype "bidirectional"))
      (node (ref "IC5") (pin "7") (pinfunction "2OUT_7") (pintype "bidirectional"))
      (node (ref "R16") (pin "1") (pinfunction "1_1") (pintype "passive"))
    )
    (net (code "46") (name "Net-(IC5-4IN+)") (class "Default")
      (node (ref "IC5") (pin "12") (pinfunction "4IN+_12") (pintype "bidirectional"))
      (node (ref "R16") (pin "2") (pinfunction "2_2") (pintype "passive"))
      (node (ref "R21") (pin "2") (pinfunction "2_2") (pintype "passive"))
    )
    (net (code "47") (name "Net-(IC5-4IN-)") (class "Default")
      (node (ref "IC5") (pin "13") (pinfunction "4IN-_13") (pintype "bidirectional"))
      (node (ref "R17") (pin "1") (pinfunction "1_1") (pintype "passive"))
      (node (ref "R19") (pin "1") (pinfunction "1_1") (pintype "passive"))
    )
    (net (code "48") (name "Net-(UC1-AVCC)") (class "Default")
      (node (ref "C3") (pin "1") (pinfunction "1_1") (pintype "passive"))
      (node (ref "L1") (pin "2") (pinfunction "2_2") (pintype "passive"))
      (node (ref "UC1") (pin "20") (pinfunction "AVCC_20") (pintype "bidirectional"))
    )
    (net (code "49") (name "Net-(UC1-PB6(XTAL1{slash}TOSC1))") (class "Default")
      (node (ref "C1") (pin "2") (pinfunction "2_2") (pintype "passive"))
      (node (ref "UC1") (pin "9") (pinfunction "PB6(XTAL1/TOSC1)_9") (pintype "bidirectional"))
      (node (ref "Y1") (pin "2") (pinfunction "2_2") (pintype "passive"))
    )
    (net (code "50") (name "Net-(UC1-PB7(XTAL2{slash}TOSC2))") (class "Default")
      (node (ref "C2") (pin "2") (pinfunction "2_2") (pintype "passive"))
      (node (ref "UC1") (pin "10") (pinfunction "PB7(XTAL2/TOSC2)_10") (pintype "bidirectional"))
      (node (ref "Y1") (pin "1") (pinfunction "1_1") (pintype "passive"))
    )
    (net (code "51") (name "unconnected-(CON4-Pad6)") (class "Default")
      (node (ref "CON4") (pin "6") (pinfunction "6_6") (pintype "passive"))
    )
    (net (code "52") (name "unconnected-(CON10-Pad1)") (class "Default")
      (node (ref "CON10") (pin "1") (pinfunction "1_1") (pintype "passive"))
    )
    (net (code "53") (name "unconnected-(CON10-Pad2)") (class "Default")
      (node (ref "CON10") (pin "2") (pinfunction "2_2") (pintype "passive"))
    )
    (net (code "54") (name "unconnected-(CON10-Pad7)") (class "Default")
      (node (ref "CON10") (pin "7") (pinfunction "7_7") (pintype "passive"))
    )
    (net (code "55") (name "unconnected-(CON10-Pad8)") (class "Default")
      (node (ref "CON10") (pin "8") (pinfunction "8_8") (pintype "passive"))
    )
    (net (code "56") (name "unconnected-(CON10-SHIELD1-Pad9)") (class "Default")
      (node (ref "CON10") (pin "9") (pinfunction "SHIELD1_9") (pintype "passive"))
    )
    (net (code "57") (name "unconnected-(CON10-SHIELD2-Pad10)") (class "Default")
      (node (ref "CON10") (pin "10") (pinfunction "SHIELD2_10") (pintype "passive"))
    )
    (net (code "58") (name "unconnected-(IC2-2A-Pad7)") (class "Default")
      (node (ref "IC2") (pin "7") (pinfunction "2A_7") (pintype "bidirectional"))
    )
    (net (code "59") (name "unconnected-(IC2-2Y-Pad6)") (class "Default")
      (node (ref "IC2") (pin "6") (pinfunction "2Y_6") (pintype "bidirectional"))
    )
    (net (code "60") (name "unconnected-(IC2-3,4EN-Pad9)") (class "Default")
      (node (ref "IC2") (pin "9") (pinfunction "3,4EN_9") (pintype "bidirectional"))
    )
    (net (code "61") (name "unconnected-(IC2-3A-Pad10)") (class "Default")
      (node (ref "IC2") (pin "10") (pinfunction "3A_10") (pintype "bidirectional"))
    )
    (net (code "62") (name "unconnected-(IC2-3Y-Pad11)") (class "Default")
      (node (ref "IC2") (pin "11") (pinfunction "3Y_11") (pintype "bidirectional"))
    )
    (net (code "63") (name "unconnected-(IC2-4A-Pad15)") (class "Default")
      (node (ref "IC2") (pin "15") (pinfunction "4A_15") (pintype "bidirectional"))
    )
    (net (code "64") (name "unconnected-(IC2-4Y-Pad14)") (class "Default")
      (node (ref "IC2") (pin "14") (pinfunction "4Y_14") (pintype "bidirectional"))
    )
    (net (code "65") (name "unconnected-(IC2-GND2-Pad5)") (class "Default")
      (node (ref "IC2") (pin "5") (pinfunction "GND2_5") (pintype "bidirectional"))
    )
    (net (code "66") (name "unconnected-(IC2-GND3-Pad13)") (class "Default")
      (node (ref "IC2") (pin "13") (pinfunction "GND3_13") (pintype "bidirectional"))
    )
    (net (code "67") (name "unconnected-(IC2-GND4-Pad12)") (class "Default")
      (node (ref "IC2") (pin "12") (pinfunction "GND4_12") (pintype "bidirectional"))
    )
    (net (code "68") (name "unconnected-(IC3-DIN2-Pad10)") (class "Default")
      (node (ref "IC3") (pin "10") (pinfunction "DIN2_10") (pintype "bidirectional"))
    )
    (net (code "69") (name "unconnected-(IC3-DOUT2-Pad7)") (class "Default")
      (node (ref "IC3") (pin "7") (pinfunction "DOUT2_7") (pintype "bidirectional"))
    )
    (net (code "70") (name "unconnected-(IC3-RIN2-Pad8)") (class "Default")
      (node (ref "IC3") (pin "8") (pinfunction "RIN2_8") (pintype "bidirectional"))
    )
    (net (code "71") (name "unconnected-(IC3-ROUT2-Pad9)") (class "Default")
      (node (ref "IC3") (pin "9") (pinfunction "ROUT2_9") (pintype "bidirectional"))
    )
    (net (code "72") (name "unconnected-(IC4-3IN+-Pad10)") (class "Default")
      (node (ref "IC4") (pin "10") (pinfunction "3IN+_10") (pintype "bidirectional"))
    )
    (net (code "73") (name "unconnected-(IC4-3IN--Pad9)") (class "Default")
      (node (ref "IC4") (pin "9") (pinfunction "3IN-_9") (pintype "bidirectional"))
    )
    (net (code "74") (name "unconnected-(IC4-3OUT-Pad8)") (class "Default")
      (node (ref "IC4") (pin "8") (pinfunction "3OUT_8") (pintype "bidirectional"))
    )
    (net (code "75") (name "unconnected-(IC5-3IN+-Pad10)") (class "Default")
      (node (ref "IC5") (pin "10") (pinfunction "3IN+_10") (pintype "bidirectional"))
    )
    (net (code "76") (name "unconnected-(IC5-3IN--Pad9)") (class "Default")
      (node (ref "IC5") (pin "9") (pinfunction "3IN-_9") (pintype "bidirectional"))
    )
    (net (code "77") (name "unconnected-(IC5-3OUT-Pad8)") (class "Default")
      (node (ref "IC5") (pin "8") (pinfunction "3OUT_8") (pintype "bidirectional"))
    )
    (net (code "78") (name "unconnected-(STEERING-WHEEL-Pad5)") (class "Default")
      (node (ref "STEERING-WHEEL") (pin "5") (pinfunction "5_5") (pintype "passive"))
    )
    (net (code "79") (name "unconnected-(STEERING-WHEEL-Pad6)") (class "Default")
      (node (ref "STEERING-WHEEL") (pin "6") (pinfunction "6_6") (pintype "passive"))
    )
    (net (code "80") (name "unconnected-(STEERING-WHEEL-Pad7)") (class "Default")
      (node (ref "STEERING-WHEEL") (pin "7") (pinfunction "7_7") (pintype "passive"))
    )
    (net (code "81") (name "unconnected-(STEERING-WHEEL-Pad8)") (class "Default")
      (node (ref "STEERING-WHEEL") (pin "8") (pinfunction "8_8") (pintype "passive"))
    )
    (net (code "82") (name "unconnected-(UC1-PB3(MOSI{slash}OC2)-Pad17)") (class "Default")
      (node (ref "UC1") (pin "17") (pinfunction "PB3(MOSI/OC2)_17") (pintype "bidirectional"))
    )
    (net (code "83") (name "unconnected-(UC1-PB4(MISO)-Pad18)") (class "Default")
      (node (ref "UC1") (pin "18") (pinfunction "PB4(MISO)_18") (pintype "bidirectional"))
    )
    (net (code "84") (name "unconnected-(UC1-PB5(SCK)-Pad19)") (class "Default")
      (node (ref "UC1") (pin "19") (pinfunction "PB5(SCK)_19") (pintype "bidirectional"))
    )
  )
)
